# blt.net
KiCad netlist of a schematic drawn in EAGLE
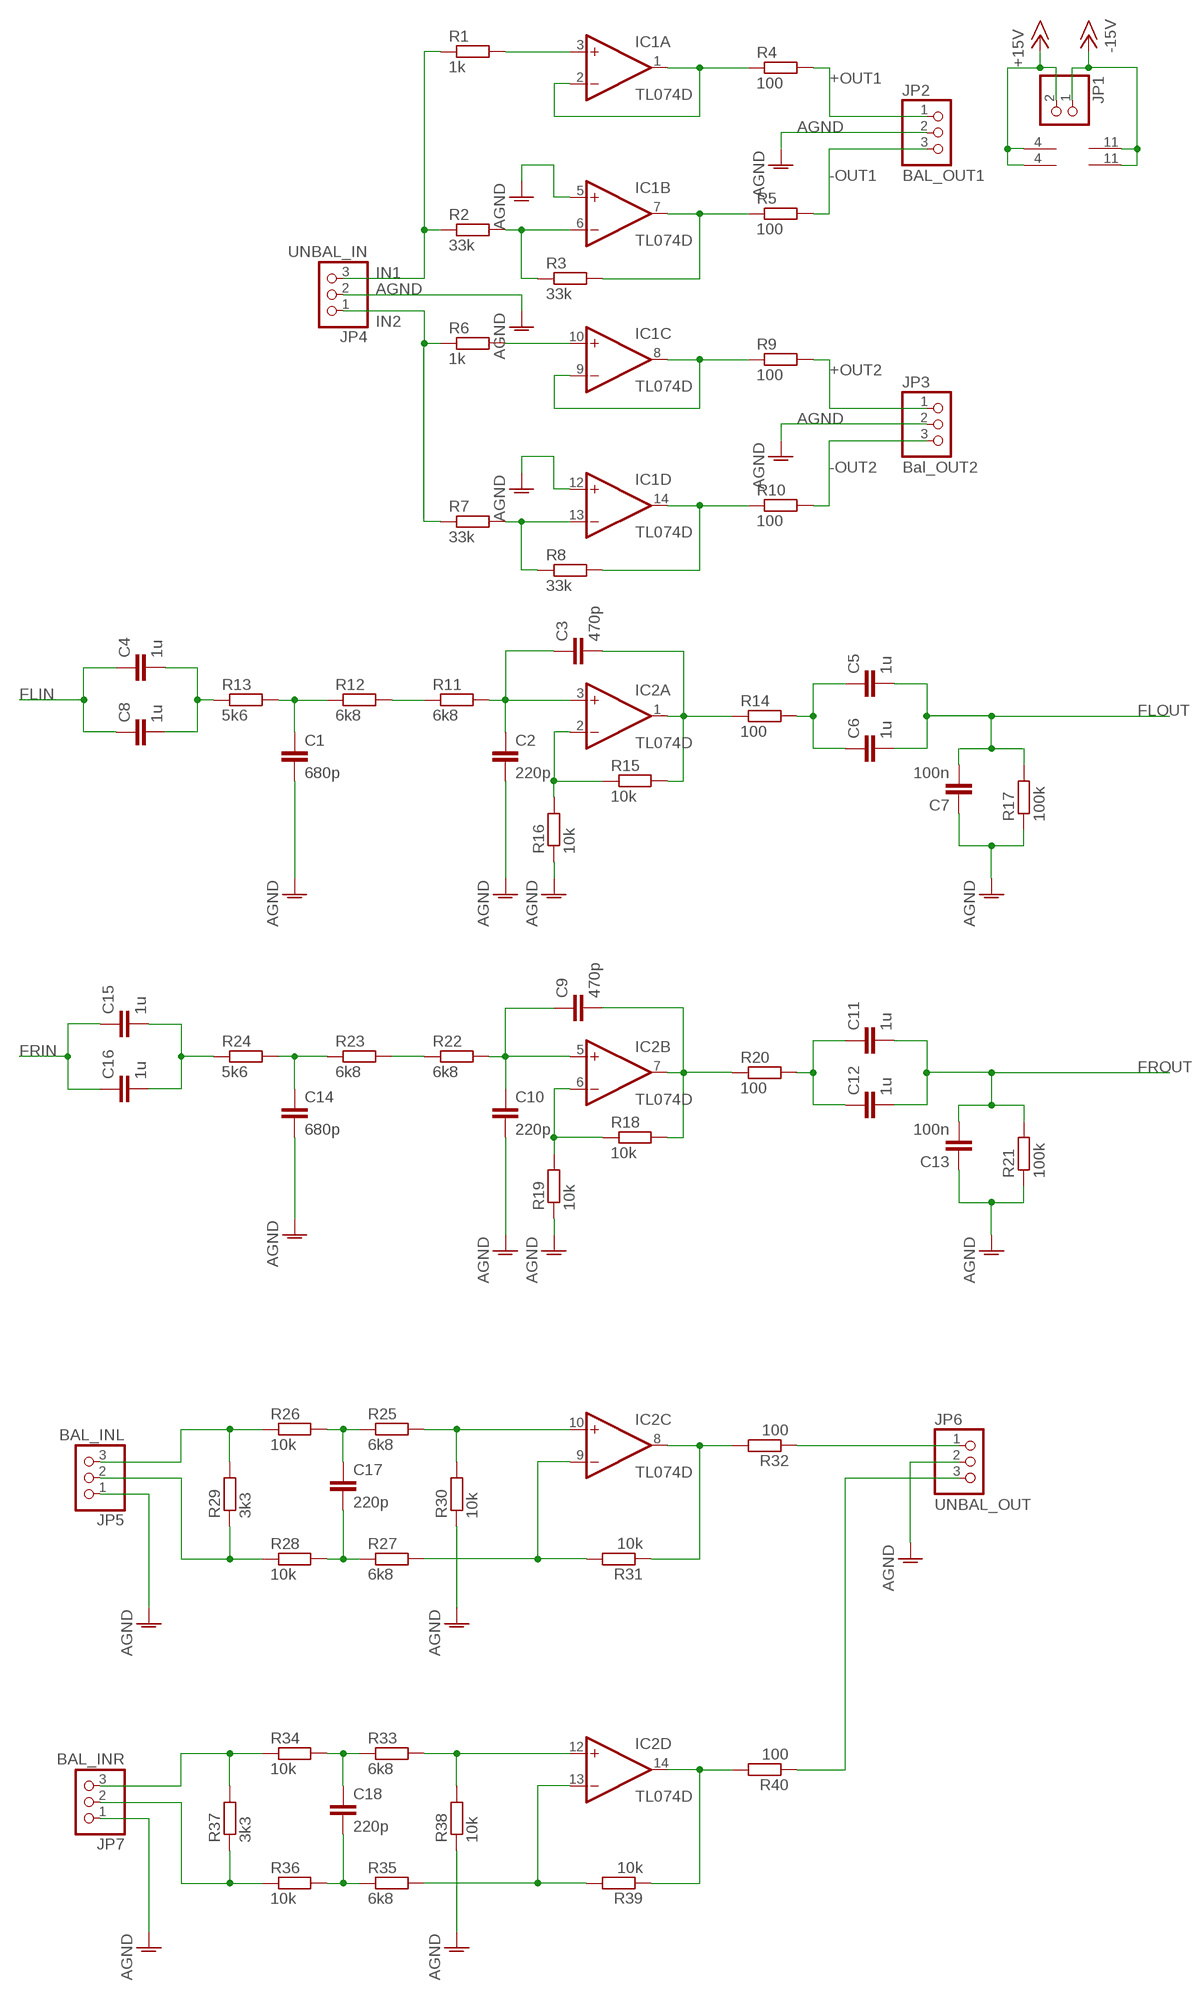
[diagram p0: schematic, sheet 1]

(export (version "E")
  (design (tool "Eeschema 10.0.6"))
  (components
    (comp (ref "C1")
      (value "680p")
      (footprint "eagle-import:C1206")
      (libsource (lib "eagle-import") (part "C-EUC1206"))
    )
    (comp (ref "C2")
      (value "220p")
      (footprint "eagle-import:C1206")
      (libsource (lib "eagle-import") (part "C-EUC1206"))
    )
    (comp (ref "C3")
      (value "470p")
      (footprint "eagle-import:C1206")
      (libsource (lib "eagle-import") (part "C-EUC1206"))
    )
    (comp (ref "C4")
      (value "1u")
      (footprint "eagle-import:C0805")
      (libsource (lib "eagle-import") (part "C-EUC0805"))
    )
    (comp (ref "C5")
      (value "1u")
      (footprint "eagle-import:C0805")
      (libsource (lib "eagle-import") (part "C-EUC0805"))
    )
    (comp (ref "C6")
      (value "1u")
      (footprint "eagle-import:C0805")
      (libsource (lib "eagle-import") (part "C-EUC0805"))
    )
    (comp (ref "C7")
      (value "100n")
      (footprint "eagle-import:C0805")
      (libsource (lib "eagle-import") (part "C-EUC0805"))
    )
    (comp (ref "C8")
      (value "1u")
      (footprint "eagle-import:C0805")
      (libsource (lib "eagle-import") (part "C-EUC0805"))
    )
    (comp (ref "C9")
      (value "470p")
      (footprint "eagle-import:C1206")
      (libsource (lib "eagle-import") (part "C-EUC1206"))
    )
    (comp (ref "C10")
      (value "220p")
      (footprint "eagle-import:C1206")
      (libsource (lib "eagle-import") (part "C-EUC1206"))
    )
    (comp (ref "C11")
      (value "1u")
      (footprint "eagle-import:C0805")
      (libsource (lib "eagle-import") (part "C-EUC0805"))
    )
    (comp (ref "C12")
      (value "1u")
      (footprint "eagle-import:C0805")
      (libsource (lib "eagle-import") (part "C-EUC0805"))
    )
    (comp (ref "C13")
      (value "100n")
      (footprint "eagle-import:C0805")
      (libsource (lib "eagle-import") (part "C-EUC0805"))
    )
    (comp (ref "C14")
      (value "680p")
      (footprint "eagle-import:C1206")
      (libsource (lib "eagle-import") (part "C-EUC1206"))
    )
    (comp (ref "C15")
      (value "1u")
      (footprint "eagle-import:C0805")
      (libsource (lib "eagle-import") (part "C-EUC0805"))
    )
    (comp (ref "C16")
      (value "1u")
      (footprint "eagle-import:C0805")
      (libsource (lib "eagle-import") (part "C-EUC0805"))
    )
    (comp (ref "C17")
      (value "220p")
      (footprint "eagle-import:C1206")
      (libsource (lib "eagle-import") (part "C-EUC1206"))
    )
    (comp (ref "C18")
      (value "220p")
      (footprint "eagle-import:C1206")
      (libsource (lib "eagle-import") (part "C-EUC1206"))
    )
    (comp (ref "IC1")
      (value "TL074D")
      (footprint "eagle-import:SO14")
      (libsource (lib "eagle-import") (part "TL074D"))
    )
    (comp (ref "IC2")
      (value "TL074D")
      (footprint "eagle-import:SO14")
      (libsource (lib "eagle-import") (part "TL074D"))
    )
    (comp (ref "JP1")
      (value "PINHD-1X2")
      (footprint "eagle-import:1X02")
      (libsource (lib "eagle-import") (part "PINHD-1X2"))
    )
    (comp (ref "JP2")
      (value "BAL_OUT1")
      (footprint "eagle-import:1X03")
      (libsource (lib "eagle-import") (part "PINHD-1X3"))
    )
    (comp (ref "JP3")
      (value "Bal_OUT2")
      (footprint "eagle-import:1X03")
      (libsource (lib "eagle-import") (part "PINHD-1X3"))
    )
    (comp (ref "JP4")
      (value "UNBAL_IN")
      (footprint "eagle-import:1X03")
      (libsource (lib "eagle-import") (part "PINHD-1X3"))
    )
    (comp (ref "JP5")
      (value "BAL_INL")
      (footprint "eagle-import:1X03")
      (libsource (lib "eagle-import") (part "PINHD-1X3"))
    )
    (comp (ref "JP6")
      (value "UNBAL_OUT")
      (footprint "eagle-import:1X03")
      (libsource (lib "eagle-import") (part "PINHD-1X3"))
    )
    (comp (ref "JP7")
      (value "BAL_INR")
      (footprint "eagle-import:1X03")
      (libsource (lib "eagle-import") (part "PINHD-1X3"))
    )
    (comp (ref "R1")
      (value "1k")
      (footprint "eagle-import:R1206")
      (libsource (lib "eagle-import") (part "R-EU_R1206"))
    )
    (comp (ref "R2")
      (value "33k")
      (footprint "eagle-import:R1206")
      (libsource (lib "eagle-import") (part "R-EU_R1206"))
    )
    (comp (ref "R3")
      (value "33k")
      (footprint "eagle-import:R1206")
      (libsource (lib "eagle-import") (part "R-EU_R1206"))
    )
    (comp (ref "R4")
      (value "100")
      (footprint "eagle-import:R1206")
      (libsource (lib "eagle-import") (part "R-EU_R1206"))
    )
    (comp (ref "R5")
      (value "100")
      (footprint "eagle-import:R1206")
      (libsource (lib "eagle-import") (part "R-EU_R1206"))
    )
    (comp (ref "R6")
      (value "1k")
      (footprint "eagle-import:R1206")
      (libsource (lib "eagle-import") (part "R-EU_R1206"))
    )
    (comp (ref "R7")
      (value "33k")
      (footprint "eagle-import:R1206")
      (libsource (lib "eagle-import") (part "R-EU_R1206"))
    )
    (comp (ref "R8")
      (value "33k")
      (footprint "eagle-import:R1206")
      (libsource (lib "eagle-import") (part "R-EU_R1206"))
    )
    (comp (ref "R9")
      (value "100")
      (footprint "eagle-import:R1206")
      (libsource (lib "eagle-import") (part "R-EU_R1206"))
    )
    (comp (ref "R10")
      (value "100")
      (footprint "eagle-import:R1206")
      (libsource (lib "eagle-import") (part "R-EU_R1206"))
    )
    (comp (ref "R11")
      (value "6k8")
      (footprint "eagle-import:R1206")
      (libsource (lib "eagle-import") (part "R-EU_R1206"))
    )
    (comp (ref "R12")
      (value "6k8")
      (footprint "eagle-import:R1206")
      (libsource (lib "eagle-import") (part "R-EU_R1206"))
    )
    (comp (ref "R13")
      (value "5k6")
      (footprint "eagle-import:R1206")
      (libsource (lib "eagle-import") (part "R-EU_R1206"))
    )
    (comp (ref "R14")
      (value "100")
      (footprint "eagle-import:R1206")
      (libsource (lib "eagle-import") (part "R-EU_R1206"))
    )
    (comp (ref "R15")
      (value "10k")
      (footprint "eagle-import:R1206")
      (libsource (lib "eagle-import") (part "R-EU_R1206"))
    )
    (comp (ref "R16")
      (value "10k")
      (footprint "eagle-import:R1206")
      (libsource (lib "eagle-import") (part "R-EU_R1206"))
    )
    (comp (ref "R17")
      (value "100k")
      (footprint "eagle-import:R1206")
      (libsource (lib "eagle-import") (part "R-EU_R1206"))
    )
    (comp (ref "R18")
      (value "10k")
      (footprint "eagle-import:R1206")
      (libsource (lib "eagle-import") (part "R-EU_R1206"))
    )
    (comp (ref "R19")
      (value "10k")
      (footprint "eagle-import:R1206")
      (libsource (lib "eagle-import") (part "R-EU_R1206"))
    )
    (comp (ref "R20")
      (value "100")
      (footprint "eagle-import:R1206")
      (libsource (lib "eagle-import") (part "R-EU_R1206"))
    )
    (comp (ref "R21")
      (value "100k")
      (footprint "eagle-import:R1206")
      (libsource (lib "eagle-import") (part "R-EU_R1206"))
    )
    (comp (ref "R22")
      (value "6k8")
      (footprint "eagle-import:R1206")
      (libsource (lib "eagle-import") (part "R-EU_R1206"))
    )
    (comp (ref "R23")
      (value "6k8")
      (footprint "eagle-import:R1206")
      (libsource (lib "eagle-import") (part "R-EU_R1206"))
    )
    (comp (ref "R24")
      (value "5k6")
      (footprint "eagle-import:R1206")
      (libsource (lib "eagle-import") (part "R-EU_R1206"))
    )
    (comp (ref "R25")
      (value "6k8")
      (footprint "eagle-import:R1206")
      (libsource (lib "eagle-import") (part "R-EU_R1206"))
    )
    (comp (ref "R26")
      (value "10k")
      (footprint "eagle-import:R1206")
      (libsource (lib "eagle-import") (part "R-EU_R1206"))
    )
    (comp (ref "R27")
      (value "6k8")
      (footprint "eagle-import:R1206")
      (libsource (lib "eagle-import") (part "R-EU_R1206"))
    )
    (comp (ref "R28")
      (value "10k")
      (footprint "eagle-import:R1206")
      (libsource (lib "eagle-import") (part "R-EU_R1206"))
    )
    (comp (ref "R29")
      (value "3k3")
      (footprint "eagle-import:R1206")
      (libsource (lib "eagle-import") (part "R-EU_R1206"))
    )
    (comp (ref "R30")
      (value "10k")
      (footprint "eagle-import:R1206")
      (libsource (lib "eagle-import") (part "R-EU_R1206"))
    )
    (comp (ref "R31")
      (value "10k")
      (footprint "eagle-import:R1206")
      (libsource (lib "eagle-import") (part "R-EU_R1206"))
    )
    (comp (ref "R32")
      (value "100")
      (footprint "eagle-import:R1206")
      (libsource (lib "eagle-import") (part "R-EU_R1206"))
    )
    (comp (ref "R33")
      (value "6k8")
      (footprint "eagle-import:R1206")
      (libsource (lib "eagle-import") (part "R-EU_R1206"))
    )
    (comp (ref "R34")
      (value "10k")
      (footprint "eagle-import:R1206")
      (libsource (lib "eagle-import") (part "R-EU_R1206"))
    )
    (comp (ref "R35")
      (value "6k8")
      (footprint "eagle-import:R1206")
      (libsource (lib "eagle-import") (part "R-EU_R1206"))
    )
    (comp (ref "R36")
      (value "10k")
      (footprint "eagle-import:R1206")
      (libsource (lib "eagle-import") (part "R-EU_R1206"))
    )
    (comp (ref "R37")
      (value "3k3")
      (footprint "eagle-import:R1206")
      (libsource (lib "eagle-import") (part "R-EU_R1206"))
    )
    (comp (ref "R38")
      (value "10k")
      (footprint "eagle-import:R1206")
      (libsource (lib "eagle-import") (part "R-EU_R1206"))
    )
    (comp (ref "R39")
      (value "10k")
      (footprint "eagle-import:R1206")
      (libsource (lib "eagle-import") (part "R-EU_R1206"))
    )
    (comp (ref "R40")
      (value "100")
      (footprint "eagle-import:R1206")
      (libsource (lib "eagle-import") (part "R-EU_R1206"))
    )
  )
  (nets
    (net (code "1") (name "+15V") (class "Default")
      (node (ref "IC1") (pin "4") (pinfunction "V+_4") (pintype "power_in"))
      (node (ref "IC2") (pin "4") (pinfunction "V+_4") (pintype "power_in"))
      (node (ref "JP1") (pin "2") (pinfunction "2_2") (pintype "passive"))
    )
    (net (code "2") (name "-15V") (class "Default")
      (node (ref "IC1") (pin "11") (pinfunction "V-_11") (pintype "power_in"))
      (node (ref "IC2") (pin "11") (pinfunction "V-_11") (pintype "power_in"))
      (node (ref "JP1") (pin "1") (pinfunction "1_1") (pintype "passive"))
    )
    (net (code "3") (name "/+OUT1") (class "Default")
      (node (ref "JP2") (pin "1") (pinfunction "1_1") (pintype "passive"))
      (node (ref "R4") (pin "2") (pinfunction "2_2") (pintype "passive"))
    )
    (net (code "4") (name "/+OUT2") (class "Default")
      (node (ref "JP3") (pin "1") (pinfunction "1_1") (pintype "passive"))
      (node (ref "R9") (pin "2") (pinfunction "2_2") (pintype "passive"))
    )
    (net (code "5") (name "/-OUT1") (class "Default")
      (node (ref "JP2") (pin "3") (pinfunction "3_3") (pintype "passive"))
      (node (ref "R5") (pin "2") (pinfunction "2_2") (pintype "passive"))
    )
    (net (code "6") (name "/-OUT2") (class "Default")
      (node (ref "JP3") (pin "3") (pinfunction "3_3") (pintype "passive"))
      (node (ref "R10") (pin "2") (pinfunction "2_2") (pintype "passive"))
    )
    (net (code "7") (name "/FLIN") (class "Default")
      (node (ref "C4") (pin "1") (pinfunction "1_1") (pintype "passive"))
      (node (ref "C8") (pin "1") (pinfunction "1_1") (pintype "passive"))
    )
    (net (code "8") (name "/FLOUT") (class "Default")
      (node (ref "C5") (pin "2") (pinfunction "2_2") (pintype "passive"))
      (node (ref "C6") (pin "2") (pinfunction "2_2") (pintype "passive"))
      (node (ref "C7") (pin "2") (pinfunction "2_2") (pintype "passive"))
      (node (ref "R17") (pin "2") (pinfunction "2_2") (pintype "passive"))
    )
    (net (code "9") (name "/FRIN") (class "Default")
      (node (ref "C15") (pin "1") (pinfunction "1_1") (pintype "passive"))
      (node (ref "C16") (pin "1") (pinfunction "1_1") (pintype "passive"))
    )
    (net (code "10") (name "/FROUT") (class "Default")
      (node (ref "C11") (pin "2") (pinfunction "2_2") (pintype "passive"))
      (node (ref "C12") (pin "2") (pinfunction "2_2") (pintype "passive"))
      (node (ref "C13") (pin "2") (pinfunction "2_2") (pintype "passive"))
      (node (ref "R21") (pin "2") (pinfunction "2_2") (pintype "passive"))
    )
    (net (code "11") (name "/IN1") (class "Default")
      (node (ref "JP4") (pin "3") (pinfunction "3_3") (pintype "passive"))
      (node (ref "R1") (pin "1") (pinfunction "1_1") (pintype "passive"))
      (node (ref "R2") (pin "1") (pinfunction "1_1") (pintype "passive"))
    )
    (net (code "12") (name "/IN2") (class "Default")
      (node (ref "JP4") (pin "1") (pinfunction "1_1") (pintype "passive"))
      (node (ref "R6") (pin "1") (pinfunction "1_1") (pintype "passive"))
      (node (ref "R7") (pin "1") (pinfunction "1_1") (pintype "passive"))
    )
    (net (code "13") (name "AGND") (class "Default")
      (node (ref "C1") (pin "2") (pinfunction "2_2") (pintype "passive"))
      (node (ref "C10") (pin "2") (pinfunction "2_2") (pintype "passive"))
      (node (ref "C13") (pin "1") (pinfunction "1_1") (pintype "passive"))
      (node (ref "C14") (pin "2") (pinfunction "2_2") (pintype "passive"))
      (node (ref "C2") (pin "2") (pinfunction "2_2") (pintype "passive"))
      (node (ref "C7") (pin "1") (pinfunction "1_1") (pintype "passive"))
      (node (ref "IC1") (pin "12") (pinfunction "+IN_12") (pintype "input"))
      (node (ref "IC1") (pin "5") (pinfunction "+IN_5") (pintype "input"))
      (node (ref "JP2") (pin "2") (pinfunction "2_2") (pintype "passive"))
      (node (ref "JP3") (pin "2") (pinfunction "2_2") (pintype "passive"))
      (node (ref "JP4") (pin "2") (pinfunction "2_2") (pintype "passive"))
      (node (ref "JP5") (pin "1") (pinfunction "1_1") (pintype "passive"))
      (node (ref "JP6") (pin "2") (pinfunction "2_2") (pintype "passive"))
      (node (ref "JP7") (pin "1") (pinfunction "1_1") (pintype "passive"))
      (node (ref "R16") (pin "1") (pinfunction "1_1") (pintype "passive"))
      (node (ref "R17") (pin "1") (pinfunction "1_1") (pintype "passive"))
      (node (ref "R19") (pin "1") (pinfunction "1_1") (pintype "passive"))
      (node (ref "R21") (pin "1") (pinfunction "1_1") (pintype "passive"))
      (node (ref "R30") (pin "1") (pinfunction "1_1") (pintype "passive"))
      (node (ref "R38") (pin "1") (pinfunction "1_1") (pintype "passive"))
    )
    (net (code "14") (name "Net-(C1-Pad1)") (class "Default")
      (node (ref "C1") (pin "1") (pinfunction "1_1") (pintype "passive"))
      (node (ref "R12") (pin "1") (pinfunction "1_1") (pintype "passive"))
      (node (ref "R13") (pin "2") (pinfunction "2_2") (pintype "passive"))
    )
    (net (code "15") (name "Net-(C4-Pad2)") (class "Default")
      (node (ref "C4") (pin "2") (pinfunction "2_2") (pintype "passive"))
      (node (ref "C8") (pin "2") (pinfunction "2_2") (pintype "passive"))
      (node (ref "R13") (pin "1") (pinfunction "1_1") (pintype "passive"))
    )
    (net (code "16") (name "Net-(C5-Pad1)") (class "Default")
      (node (ref "C5") (pin "1") (pinfunction "1_1") (pintype "passive"))
      (node (ref "C6") (pin "1") (pinfunction "1_1") (pintype "passive"))
      (node (ref "R14") (pin "2") (pinfunction "2_2") (pintype "passive"))
    )
    (net (code "17") (name "Net-(C11-Pad1)") (class "Default")
      (node (ref "C11") (pin "1") (pinfunction "1_1") (pintype "passive"))
      (node (ref "C12") (pin "1") (pinfunction "1_1") (pintype "passive"))
      (node (ref "R20") (pin "2") (pinfunction "2_2") (pintype "passive"))
    )
    (net (code "18") (name "Net-(C14-Pad1)") (class "Default")
      (node (ref "C14") (pin "1") (pinfunction "1_1") (pintype "passive"))
      (node (ref "R23") (pin "1") (pinfunction "1_1") (pintype "passive"))
      (node (ref "R24") (pin "2") (pinfunction "2_2") (pintype "passive"))
    )
    (net (code "19") (name "Net-(C15-Pad2)") (class "Default")
      (node (ref "C15") (pin "2") (pinfunction "2_2") (pintype "passive"))
      (node (ref "C16") (pin "2") (pinfunction "2_2") (pintype "passive"))
      (node (ref "R24") (pin "1") (pinfunction "1_1") (pintype "passive"))
    )
    (net (code "20") (name "Net-(C17-Pad1)") (class "Default")
      (node (ref "C17") (pin "1") (pinfunction "1_1") (pintype "passive"))
      (node (ref "R25") (pin "1") (pinfunction "1_1") (pintype "passive"))
      (node (ref "R26") (pin "2") (pinfunction "2_2") (pintype "passive"))
    )
    (net (code "21") (name "Net-(C17-Pad2)") (class "Default")
      (node (ref "C17") (pin "2") (pinfunction "2_2") (pintype "passive"))
      (node (ref "R27") (pin "1") (pinfunction "1_1") (pintype "passive"))
      (node (ref "R28") (pin "2") (pinfunction "2_2") (pintype "passive"))
    )
    (net (code "22") (name "Net-(C18-Pad1)") (class "Default")
      (node (ref "C18") (pin "1") (pinfunction "1_1") (pintype "passive"))
      (node (ref "R33") (pin "1") (pinfunction "1_1") (pintype "passive"))
      (node (ref "R34") (pin "2") (pinfunction "2_2") (pintype "passive"))
    )
    (net (code "23") (name "Net-(C18-Pad2)") (class "Default")
      (node (ref "C18") (pin "2") (pinfunction "2_2") (pintype "passive"))
      (node (ref "R35") (pin "1") (pinfunction "1_1") (pintype "passive"))
      (node (ref "R36") (pin "2") (pinfunction "2_2") (pintype "passive"))
    )
    (net (code "24") (name "Net-(IC1A-+IN)") (class "Default")
      (node (ref "IC1") (pin "3") (pinfunction "+IN_3") (pintype "input"))
      (node (ref "R1") (pin "2") (pinfunction "2_2") (pintype "passive"))
    )
    (net (code "25") (name "Net-(IC1A--IN)") (class "Default")
      (node (ref "IC1") (pin "1") (pinfunction "OUT_1") (pintype "output"))
      (node (ref "IC1") (pin "2") (pinfunction "-IN_2") (pintype "input"))
      (node (ref "R4") (pin "1") (pinfunction "1_1") (pintype "passive"))
    )
    (net (code "26") (name "Net-(IC1B--IN)") (class "Default")
      (node (ref "IC1") (pin "6") (pinfunction "-IN_6") (pintype "input"))
      (node (ref "R2") (pin "2") (pinfunction "2_2") (pintype "passive"))
      (node (ref "R3") (pin "1") (pinfunction "1_1") (pintype "passive"))
    )
    (net (code "27") (name "Net-(IC1B-OUT)") (class "Default")
      (node (ref "IC1") (pin "7") (pinfunction "OUT_7") (pintype "output"))
      (node (ref "R3") (pin "2") (pinfunction "2_2") (pintype "passive"))
      (node (ref "R5") (pin "1") (pinfunction "1_1") (pintype "passive"))
    )
    (net (code "28") (name "Net-(IC1C-+IN)") (class "Default")
      (node (ref "IC1") (pin "10") (pinfunction "+IN_10") (pintype "input"))
      (node (ref "R6") (pin "2") (pinfunction "2_2") (pintype "passive"))
    )
    (net (code "29") (name "Net-(IC1C--IN)") (class "Default")
      (node (ref "IC1") (pin "8") (pinfunction "OUT_8") (pintype "output"))
      (node (ref "IC1") (pin "9") (pinfunction "-IN_9") (pintype "input"))
      (node (ref "R9") (pin "1") (pinfunction "1_1") (pintype "passive"))
    )
    (net (code "30") (name "Net-(IC1D--IN)") (class "Default")
      (node (ref "IC1") (pin "13") (pinfunction "-IN_13") (pintype "input"))
      (node (ref "R7") (pin "2") (pinfunction "2_2") (pintype "passive"))
      (node (ref "R8") (pin "1") (pinfunction "1_1") (pintype "passive"))
    )
    (net (code "31") (name "Net-(IC1D-OUT)") (class "Default")
      (node (ref "IC1") (pin "14") (pinfunction "OUT_14") (pintype "output"))
      (node (ref "R10") (pin "1") (pinfunction "1_1") (pintype "passive"))
      (node (ref "R8") (pin "2") (pinfunction "2_2") (pintype "passive"))
    )
    (net (code "32") (name "Net-(IC2A-+IN)") (class "Default")
      (node (ref "C2") (pin "1") (pinfunction "1_1") (pintype "passive"))
      (node (ref "C3") (pin "1") (pinfunction "1_1") (pintype "passive"))
      (node (ref "IC2") (pin "3") (pinfunction "+IN_3") (pintype "input"))
      (node (ref "R11") (pin "2") (pinfunction "2_2") (pintype "passive"))
    )
    (net (code "33") (name "Net-(IC2A--IN)") (class "Default")
      (node (ref "IC2") (pin "2") (pinfunction "-IN_2") (pintype "input"))
      (node (ref "R15") (pin "1") (pinfunction "1_1") (pintype "passive"))
      (node (ref "R16") (pin "2") (pinfunction "2_2") (pintype "passive"))
    )
    (net (code "34") (name "Net-(IC2A-OUT)") (class "Default")
      (node (ref "C3") (pin "2") (pinfunction "2_2") (pintype "passive"))
      (node (ref "IC2") (pin "1") (pinfunction "OUT_1") (pintype "output"))
      (node (ref "R14") (pin "1") (pinfunction "1_1") (pintype "passive"))
      (node (ref "R15") (pin "2") (pinfunction "2_2") (pintype "passive"))
    )
    (net (code "35") (name "Net-(IC2B-+IN)") (class "Default")
      (node (ref "C10") (pin "1") (pinfunction "1_1") (pintype "passive"))
      (node (ref "C9") (pin "1") (pinfunction "1_1") (pintype "passive"))
      (node (ref "IC2") (pin "5") (pinfunction "+IN_5") (pintype "input"))
      (node (ref "R22") (pin "2") (pinfunction "2_2") (pintype "passive"))
    )
    (net (code "36") (name "Net-(IC2B--IN)") (class "Default")
      (node (ref "IC2") (pin "6") (pinfunction "-IN_6") (pintype "input"))
      (node (ref "R18") (pin "1") (pinfunction "1_1") (pintype "passive"))
      (node (ref "R19") (pin "2") (pinfunction "2_2") (pintype "passive"))
    )
    (net (code "37") (name "Net-(IC2B-OUT)") (class "Default")
      (node (ref "C9") (pin "2") (pinfunction "2_2") (pintype "passive"))
      (node (ref "IC2") (pin "7") (pinfunction "OUT_7") (pintype "output"))
      (node (ref "R18") (pin "2") (pinfunction "2_2") (pintype "passive"))
      (node (ref "R20") (pin "1") (pinfunction "1_1") (pintype "passive"))
    )
    (net (code "38") (name "Net-(IC2C-+IN)") (class "Default")
      (node (ref "IC2") (pin "10") (pinfunction "+IN_10") (pintype "input"))
      (node (ref "R25") (pin "2") (pinfunction "2_2") (pintype "passive"))
      (node (ref "R30") (pin "2") (pinfunction "2_2") (pintype "passive"))
    )
    (net (code "39") (name "Net-(IC2C--IN)") (class "Default")
      (node (ref "IC2") (pin "9") (pinfunction "-IN_9") (pintype "input"))
      (node (ref "R27") (pin "2") (pinfunction "2_2") (pintype "passive"))
      (node (ref "R31") (pin "2") (pinfunction "2_2") (pintype "passive"))
    )
    (net (code "40") (name "Net-(IC2C-OUT)") (class "Default")
      (node (ref "IC2") (pin "8") (pinfunction "OUT_8") (pintype "output"))
      (node (ref "R31") (pin "1") (pinfunction "1_1") (pintype "passive"))
      (node (ref "R32") (pin "2") (pinfunction "2_2") (pintype "passive"))
    )
    (net (code "41") (name "Net-(IC2D-+IN)") (class "Default")
      (node (ref "IC2") (pin "12") (pinfunction "+IN_12") (pintype "input"))
      (node (ref "R33") (pin "2") (pinfunction "2_2") (pintype "passive"))
      (node (ref "R38") (pin "2") (pinfunction "2_2") (pintype "passive"))
    )
    (net (code "42") (name "Net-(IC2D--IN)") (class "Default")
      (node (ref "IC2") (pin "13") (pinfunction "-IN_13") (pintype "input"))
      (node (ref "R35") (pin "2") (pinfunction "2_2") (pintype "passive"))
      (node (ref "R39") (pin "2") (pinfunction "2_2") (pintype "passive"))
    )
    (net (code "43") (name "Net-(IC2D-OUT)") (class "Default")
      (node (ref "IC2") (pin "14") (pinfunction "OUT_14") (pintype "output"))
      (node (ref "R39") (pin "1") (pinfunction "1_1") (pintype "passive"))
      (node (ref "R40") (pin "2") (pinfunction "2_2") (pintype "passive"))
    )
    (net (code "44") (name "Net-(JP5-Pad2)") (class "Default")
      (node (ref "JP5") (pin "2") (pinfunction "2_2") (pintype "passive"))
      (node (ref "R28") (pin "1") (pinfunction "1_1") (pintype "passive"))
      (node (ref "R29") (pin "1") (pinfunction "1_1") (pintype "passive"))
    )
    (net (code "45") (name "Net-(JP5-Pad3)") (class "Default")
      (node (ref "JP5") (pin "3") (pinfunction "3_3") (pintype "passive"))
      (node (ref "R26") (pin "1") (pinfunction "1_1") (pintype "passive"))
      (node (ref "R29") (pin "2") (pinfunction "2_2") (pintype "passive"))
    )
    (net (code "46") (name "Net-(JP6-Pad1)") (class "Default")
      (node (ref "JP6") (pin "1") (pinfunction "1_1") (pintype "passive"))
      (node (ref "R32") (pin "1") (pinfunction "1_1") (pintype "passive"))
    )
    (net (code "47") (name "Net-(JP6-Pad3)") (class "Default")
      (node (ref "JP6") (pin "3") (pinfunction "3_3") (pintype "passive"))
      (node (ref "R40") (pin "1") (pinfunction "1_1") (pintype "passive"))
    )
    (net (code "48") (name "Net-(JP7-Pad2)") (class "Default")
      (node (ref "JP7") (pin "2") (pinfunction "2_2") (pintype "passive"))
      (node (ref "R36") (pin "1") (pinfunction "1_1") (pintype "passive"))
      (node (ref "R37") (pin "1") (pinfunction "1_1") (pintype "passive"))
    )
    (net (code "49") (name "Net-(JP7-Pad3)") (class "Default")
      (node (ref "JP7") (pin "3") (pinfunction "3_3") (pintype "passive"))
      (node (ref "R34") (pin "1") (pinfunction "1_1") (pintype "passive"))
      (node (ref "R37") (pin "2") (pinfunction "2_2") (pintype "passive"))
    )
    (net (code "50") (name "Net-(R11-Pad1)") (class "Default")
      (node (ref "R11") (pin "1") (pinfunction "1_1") (pintype "passive"))
      (node (ref "R12") (pin "2") (pinfunction "2_2") (pintype "passive"))
    )
    (net (code "51") (name "Net-(R22-Pad1)") (class "Default")
      (node (ref "R22") (pin "1") (pinfunction "1_1") (pintype "passive"))
      (node (ref "R23") (pin "2") (pinfunction "2_2") (pintype "passive"))
    )
  )
)
